# QG-2864KSWEG01_OLED_Display_Module.net
KiCad netlist of a schematic drawn in Altium Designer
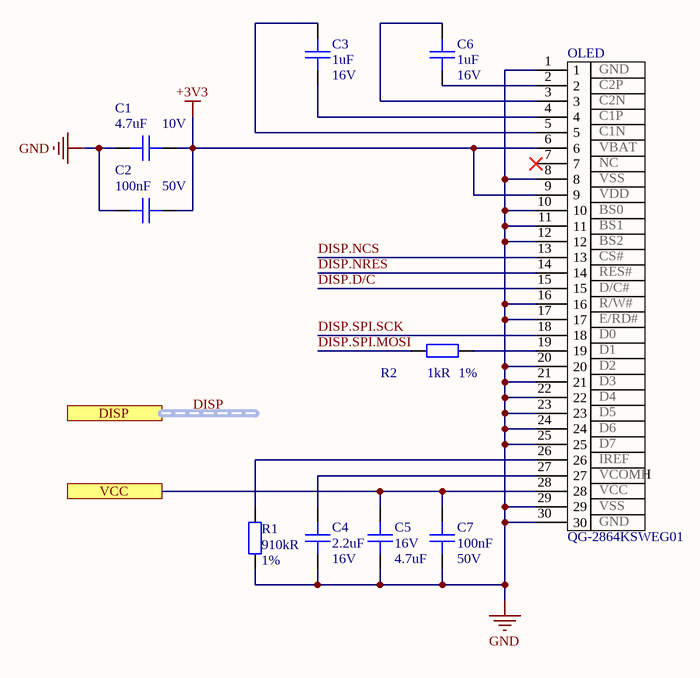
[diagram p0: QG-2864KSWEG01_OLED_Display_Module.SchDoc]

(export (version "E")
  (design (tool "Eeschema 10.0.6"))
  (components
    (comp (ref "C1")
      (value "CAP CER 4.7UF 10V X5R 0603")
      (footprint "C0603")
      (description "4.7µF ±10% 10V Ceramic Capacitor X5R 0603 (1608 Metric)")
      (fields
        (field (name "MANUFACTURER") "Yageo")
        (field (name "MANUFACTURER PART NUMBER") "CC0603KRX5R6BB475")
        (field (name "VOLTAGE RATING") "10V")
        (field (name "CAPACITANCE") "4.7uF")
      )
      (libsource (lib "capacitors_smd") (part "CAP CER 4.7UF 10V X5R 0603"))
    )
    (comp (ref "C2")
      (value "CAP CER 0.1UF 50V X7R 0402")
      (footprint "C0402")
      (description "0.1µF ±10% 50V Ceramic Capacitor X7R 0402 (1005 Metric)")
      (fields
        (field (name "MANUFACTURER PART NUMBER") "CGA2B3X7R1H104K050BB")
        (field (name "MANUFACTURER") "TDK")
        (field (name "CAPACITANCE") "100nF")
        (field (name "VOLTAGE") "50V")
      )
      (libsource (lib "capacitors_smd") (part "CAP CER 0.1UF 50V X7R 0402"))
    )
    (comp (ref "C3")
      (value "CAP CER 1UF 16V X5R 0603")
      (footprint "C0603")
      (description "1µF ±10% 16V Ceramic Capacitor X5R 0603 (1608 Metric)")
      (fields
        (field (name "MANUFACTURER") "Yageo")
        (field (name "MANUFACTURER PART NUMBER") "CC0603KRX5R7BB105")
        (field (name "CAPACITANCE") "1uF")
        (field (name "VOLTAGE RATING") "16V")
      )
      (libsource (lib "capacitors_smd") (part "CAP CER 1UF 16V X5R 0603"))
    )
    (comp (ref "C4")
      (value "CAP CER 2.2UF 16V X5R 0603")
      (footprint "C0603")
      (description "2.2µF ±10% 16V Ceramic Capacitor X5R 0603 (1608 Metric)")
      (fields
        (field (name "MANUFACTURER") "Yageo")
        (field (name "MANUFACTURER PART NUMBER") "CC0603KRX5R7BB225")
        (field (name "CAPACITANCE") "2.2uF")
        (field (name "VOLTAGE RATING") "16V")
      )
      (libsource (lib "capacitors_smd") (part "CAP CER 2.2UF 16V X5R 0603"))
    )
    (comp (ref "C5")
      (value "CAP CER 4.7UF 16V X5R 0603")
      (footprint "C0603")
      (description "4.7µF ±10% 16V Ceramic Capacitor X5R 0603 (1608 Metric)")
      (fields
        (field (name "MANUFACTURER") "Yageo")
        (field (name "MANUFACTURER PART NUMBER") "CC0603KRX5R7BB475")
        (field (name "VOLTAGE RATING") "16V")
        (field (name "CAPACITANCE") "4.7uF")
      )
      (libsource (lib "capacitors_smd") (part "CAP CER 4.7UF 16V X5R 0603"))
    )
    (comp (ref "C6")
      (value "CAP CER 1UF 16V X5R 0603")
      (footprint "C0603")
      (description "1µF ±10% 16V Ceramic Capacitor X5R 0603 (1608 Metric)")
      (fields
        (field (name "MANUFACTURER") "Yageo")
        (field (name "MANUFACTURER PART NUMBER") "CC0603KRX5R7BB105")
        (field (name "CAPACITANCE") "1uF")
        (field (name "VOLTAGE RATING") "16V")
      )
      (libsource (lib "capacitors_smd") (part "CAP CER 1UF 16V X5R 0603"))
    )
    (comp (ref "C7")
      (value "CAP CER 0.1UF 50V X7R 0402")
      (footprint "C0402")
      (description "0.1µF ±10% 50V Ceramic Capacitor X7R 0402 (1005 Metric)")
      (fields
        (field (name "MANUFACTURER PART NUMBER") "CGA2B3X7R1H104K050BB")
        (field (name "MANUFACTURER") "TDK")
        (field (name "CAPACITANCE") "100nF")
        (field (name "VOLTAGE") "50V")
      )
      (libsource (lib "capacitors_smd") (part "CAP CER 0.1UF 50V X7R 0402"))
    )
    (comp (ref "OLED")
      (value "QG-2864KSWEG01")
      (footprint "QG-2864KSWEG01_FRONT")
      (description "OLED Display Module FPC #LT1306P22 TOP 30P 0.7MM")
      (fields
        (field (name "MANUFACTURER") "Limito Technology Inc.")
        (field (name "PIN_1") "GND")
        (field (name "PIN_2") "C2P")
        (field (name "PIN_3") "C2N")
        (field (name "PIN_4") "C1P")
        (field (name "PIN_5") "C1N")
        (field (name "PIN_6") "VBAT")
        (field (name "PIN_7") "NC")
        (field (name "PIN_8") "VSS")
        (field (name "PIN_9") "VDD")
        (field (name "PIN_10") "BS0")
        (field (name "PIN_11") "BS1")
        (field (name "PIN_12") "BS2")
        (field (name "PIN_13") "CS#")
        (field (name "PIN_14") "RES#")
        (field (name "PIN_15") "D/C#")
        (field (name "PIN_16") "R/W#")
        (field (name "PIN_17") "E/RD#")
        (field (name "PIN_18") "D0")
        (field (name "PIN_19") "D1")
        (field (name "PIN_20") "D2")
        (field (name "PIN_21") "D3")
        (field (name "PIN_22") "D4")
        (field (name "PIN_23") "D5")
        (field (name "PIN_24") "D6")
        (field (name "PIN_25") "D7")
        (field (name "PIN_26") "IREF")
        (field (name "PIN_27") "VCOMH")
        (field (name "PIN_28") "VCC")
        (field (name "PIN_29") "VSS")
        (field (name "PIN_30") "GND")
      )
      (libsource (lib "Control_Board_Model") (part "MOD QG-2864KSWEG01 OLED DISPLAY"))
    )
    (comp (ref "R1")
      (value "RES SMD 910K OHM 1% 1/16W 0402")
      (footprint "R0402")
      (description "910 kOhms ±1% 0.063W, 1/16W Chip Resistor 0402 (1005 Metric) Moisture Resistant Thick Film")
      (fields
        (field (name "MANUFACTURER") "Yageo")
        (field (name "MANUFACTURER PART NUMBER") "RC0402FR-07910KL")
        (field (name "RESISTANCE") "910kR")
        (field (name "TOLERANCE") "1%")
      )
      (libsource (lib "resistors_smd") (part "RES SMD 910K OHM 1% 1/16W 0402"))
    )
    (comp (ref "R2")
      (value "RES SMD 1K OHM 1% 1/16W 0402")
      (footprint "R0402")
      (description "1 kOhms ±1% 0.063W, 1/16W Chip Resistor 0402 (1005 Metric) Moisture Resistant Thick Film")
      (fields
        (field (name "MANUFACTURER") "Yageo")
        (field (name "MANUFACTURER PART NUMBER") "RC0402FR-071KL")
        (field (name "TOLERANCE") "1%")
        (field (name "RESISTANCE") "1kR")
      )
      (libsource (lib "resistors_smd") (part "RES SMD 1K OHM 1% 1/16W 0402"))
    )
  )
  (nets
    (net (code "2") (name "+3V3") (class "Default")
      (node (ref "C1") (pin "1") (pinfunction "1_1") (pintype "passive"))
      (node (ref "C2") (pin "1") (pinfunction "1_1") (pintype "passive"))
      (node (ref "OLED") (pin "6") (pinfunction "6_6") (pintype "passive"))
      (node (ref "OLED") (pin "9") (pinfunction "9_9") (pintype "passive"))
    )
    (net (code "3") (name "/DISP.D{slash}C") (class "Default")
      (node (ref "OLED") (pin "15") (pinfunction "15_15") (pintype "passive"))
    )
    (net (code "4") (name "/DISP.NCS") (class "Default")
      (node (ref "OLED") (pin "13") (pinfunction "13_13") (pintype "passive"))
    )
    (net (code "5") (name "/DISP.NRES") (class "Default")
      (node (ref "OLED") (pin "14") (pinfunction "14_14") (pintype "passive"))
    )
    (net (code "6") (name "/DISP.SPI.MOSI") (class "Default")
      (node (ref "R2") (pin "1") (pinfunction "1_1") (pintype "passive"))
    )
    (net (code "7") (name "/DISP.SPI.SCK") (class "Default")
      (node (ref "OLED") (pin "18") (pinfunction "18_18") (pintype "passive"))
    )
    (net (code "8") (name "/VCC") (class "Default")
      (node (ref "C5") (pin "1") (pinfunction "1_1") (pintype "passive"))
      (node (ref "C7") (pin "1") (pinfunction "1_1") (pintype "passive"))
      (node (ref "OLED") (pin "28") (pinfunction "28_28") (pintype "passive"))
    )
    (net (code "10") (name "GND") (class "Default")
      (node (ref "C1") (pin "2") (pinfunction "2_2") (pintype "passive"))
      (node (ref "C2") (pin "2") (pinfunction "2_2") (pintype "passive"))
      (node (ref "C4") (pin "1") (pinfunction "1_1") (pintype "passive"))
      (node (ref "C5") (pin "2") (pinfunction "2_2") (pintype "passive"))
      (node (ref "C7") (pin "2") (pinfunction "2_2") (pintype "passive"))
      (node (ref "OLED") (pin "1") (pinfunction "1_1") (pintype "passive"))
      (node (ref "OLED") (pin "10") (pinfunction "10_10") (pintype "passive"))
      (node (ref "OLED") (pin "11") (pinfunction "11_11") (pintype "passive"))
      (node (ref "OLED") (pin "12") (pinfunction "12_12") (pintype "passive"))
      (node (ref "OLED") (pin "16") (pinfunction "16_16") (pintype "passive"))
      (node (ref "OLED") (pin "17") (pinfunction "17_17") (pintype "passive"))
      (node (ref "OLED") (pin "20") (pinfunction "20_20") (pintype "passive"))
      (node (ref "OLED") (pin "21") (pinfunction "21_21") (pintype "passive"))
      (node (ref "OLED") (pin "22") (pinfunction "22_22") (pintype "passive"))
      (node (ref "OLED") (pin "23") (pinfunction "23_23") (pintype "passive"))
      (node (ref "OLED") (pin "24") (pinfunction "24_24") (pintype "passive"))
      (node (ref "OLED") (pin "25") (pinfunction "25_25") (pintype "passive"))
      (node (ref "OLED") (pin "29") (pinfunction "29_29") (pintype "passive"))
      (node (ref "OLED") (pin "30") (pinfunction "30_30") (pintype "passive"))
      (node (ref "OLED") (pin "8") (pinfunction "8_8") (pintype "passive"))
      (node (ref "R1") (pin "2") (pinfunction "2_2") (pintype "passive"))
    )
    (net (code "11") (name "Net-(C3-Pad1)") (class "Default")
      (node (ref "C3") (pin "1") (pinfunction "1_1") (pintype "passive"))
      (node (ref "OLED") (pin "4") (pinfunction "4_4") (pintype "passive"))
    )
    (net (code "12") (name "Net-(C3-Pad2)") (class "Default")
      (node (ref "C3") (pin "2") (pinfunction "2_2") (pintype "passive"))
      (node (ref "OLED") (pin "5") (pinfunction "5_5") (pintype "passive"))
    )
    (net (code "13") (name "Net-(C4-Pad2)") (class "Default")
      (node (ref "C4") (pin "2") (pinfunction "2_2") (pintype "passive"))
      (node (ref "OLED") (pin "27") (pinfunction "27_27") (pintype "passive"))
    )
    (net (code "14") (name "Net-(C6-Pad1)") (class "Default")
      (node (ref "C6") (pin "1") (pinfunction "1_1") (pintype "passive"))
      (node (ref "OLED") (pin "2") (pinfunction "2_2") (pintype "passive"))
    )
    (net (code "15") (name "Net-(C6-Pad2)") (class "Default")
      (node (ref "C6") (pin "2") (pinfunction "2_2") (pintype "passive"))
      (node (ref "OLED") (pin "3") (pinfunction "3_3") (pintype "passive"))
    )
    (net (code "16") (name "Net-(OLED-Pad19)") (class "Default")
      (node (ref "OLED") (pin "19") (pinfunction "19_19") (pintype "passive"))
      (node (ref "R2") (pin "2") (pinfunction "2_2") (pintype "passive"))
    )
    (net (code "17") (name "Net-(OLED-Pad26)") (class "Default")
      (node (ref "OLED") (pin "26") (pinfunction "26_26") (pintype "passive"))
      (node (ref "R1") (pin "1") (pinfunction "1_1") (pintype "passive"))
    )
    (net (code "18") (name "unconnected-(OLED-Pad7)") (class "Default")
      (node (ref "OLED") (pin "7") (pinfunction "7_7") (pintype "passive+no_connect"))
    )
  )
)
